# espIntrepid.net
KiCad netlist of a schematic drawn in EAGLE
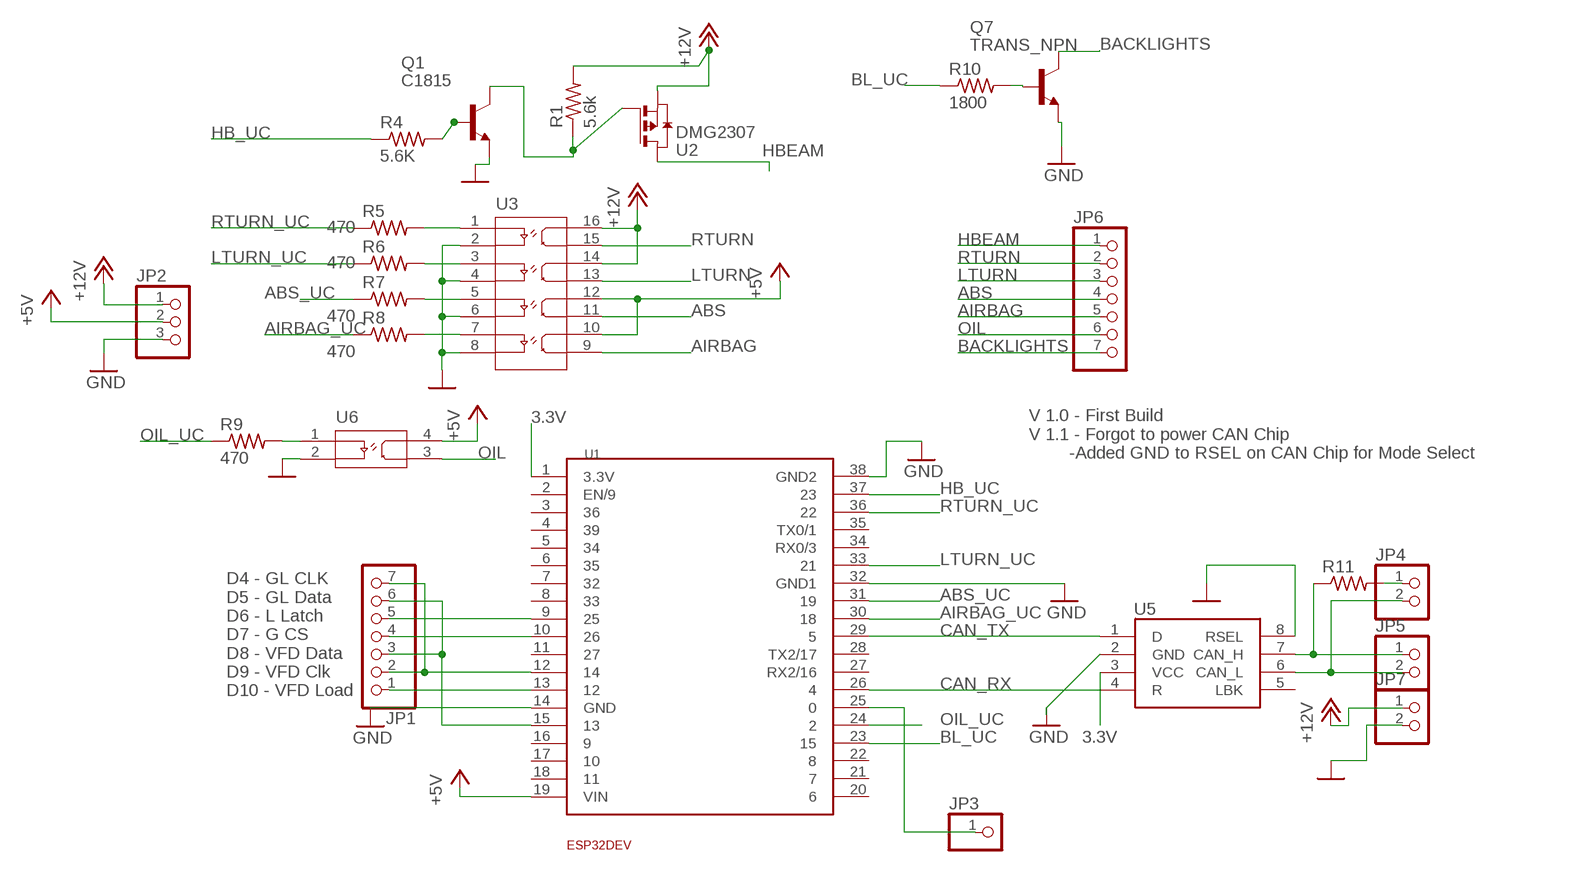
[diagram p0: schematic, sheet 1]

(export (version "E")
  (design (tool "Eeschema 10.0.6"))
  (components
    (comp (ref "JP1")
      (value "PINHD-1X7")
      (footprint "eagle-import:1X07")
      (libsource (lib "eagle-import") (part "PINHD-1X7"))
    )
    (comp (ref "JP2")
      (value "PINHD-1X3")
      (footprint "eagle-import:1X03")
      (libsource (lib "eagle-import") (part "PINHD-1X3"))
    )
    (comp (ref "JP3")
      (value "PINHD-1X1")
      (footprint "eagle-import:1X01")
      (libsource (lib "eagle-import") (part "PINHD-1X1"))
    )
    (comp (ref "JP4")
      (value "PINHD-1X2")
      (footprint "eagle-import:1X02")
      (libsource (lib "eagle-import") (part "PINHD-1X2"))
    )
    (comp (ref "JP5")
      (value "PINHD-1X2")
      (footprint "eagle-import:1X02")
      (libsource (lib "eagle-import") (part "PINHD-1X2"))
    )
    (comp (ref "JP6")
      (value "PINHD-1X7")
      (footprint "eagle-import:1X07")
      (libsource (lib "eagle-import") (part "pinhead_325_PINHD-1X7"))
    )
    (comp (ref "JP7")
      (value "PINHD-1X2")
      (footprint "eagle-import:1X02")
      (libsource (lib "eagle-import") (part "PINHD-1X2"))
    )
    (comp (ref "Q1")
      (value "C1815")
      (footprint "eagle-import:SOT-23")
      (libsource (lib "eagle-import") (part "TRANS_NPN"))
    )
    (comp (ref "Q7")
      (value "TRANS_NPN")
      (footprint "eagle-import:SOT-23")
      (libsource (lib "eagle-import") (part "TRANS_NPN"))
    )
    (comp (ref "R1")
      (value "5.6k")
      (footprint "eagle-import:M1206")
      (libsource (lib "eagle-import") (part "R-US_M1206"))
    )
    (comp (ref "R4")
      (value "5.6K")
      (footprint "eagle-import:M1206")
      (libsource (lib "eagle-import") (part "R-US_M1206"))
    )
    (comp (ref "R5")
      (value "470")
      (footprint "eagle-import:M1206")
      (libsource (lib "eagle-import") (part "R-US_M1206"))
    )
    (comp (ref "R6")
      (value "470")
      (footprint "eagle-import:M1206")
      (libsource (lib "eagle-import") (part "R-US_M1206"))
    )
    (comp (ref "R7")
      (value "470")
      (footprint "eagle-import:M1206")
      (libsource (lib "eagle-import") (part "R-US_M1206"))
    )
    (comp (ref "R8")
      (value "470")
      (footprint "eagle-import:M1206")
      (libsource (lib "eagle-import") (part "R-US_M1206"))
    )
    (comp (ref "R9")
      (value "470")
      (footprint "eagle-import:M1206")
      (libsource (lib "eagle-import") (part "R-US_M1206"))
    )
    (comp (ref "R10")
      (value "1800")
      (footprint "eagle-import:M1206")
      (libsource (lib "eagle-import") (part "R-US_M1206"))
    )
    (comp (ref "R11")
      (value "R-US_M1206")
      (footprint "eagle-import:M1206")
      (libsource (lib "eagle-import") (part "R-US_M1206"))
    )
    (comp (ref "U1")
      (value "ESP32DEV_38")
      (footprint "eagle-import:ESP32DEV_38")
      (libsource (lib "eagle-import") (part "ESP32DEV_38"))
    )
    (comp (ref "U2")
      (value "DMG2307")
      (footprint "eagle-import:SOT-23")
      (libsource (lib "eagle-import") (part "MOSFET_P"))
    )
    (comp (ref "U3")
      (value "LTV-847")
      (footprint "eagle-import:SM-16")
      (libsource (lib "eagle-import") (part "LTV-847"))
    )
    (comp (ref "U5")
      (value "SN65HVD233D")
      (footprint "eagle-import:SOIC-8")
      (libsource (lib "eagle-import") (part "SN65HVD233D"))
    )
    (comp (ref "U6")
      (value "LTV-817")
      (footprint "eagle-import:SM-4")
      (libsource (lib "eagle-import") (part "LTV-817"))
    )
  )
  (nets
    (net (code "1") (name "+5V") (class "Default")
      (node (ref "JP2") (pin "2") (pinfunction "2_2") (pintype "passive"))
      (node (ref "U1") (pin "19") (pinfunction "VIN_19") (pintype "bidirectional"))
      (node (ref "U3") (pin "10") (pinfunction "P$10_10") (pintype "bidirectional"))
      (node (ref "U3") (pin "12") (pinfunction "P$12_12") (pintype "bidirectional"))
      (node (ref "U6") (pin "4") (pinfunction "P$4_4") (pintype "bidirectional"))
    )
    (net (code "2") (name "+12V") (class "Default")
      (node (ref "JP2") (pin "1") (pinfunction "1_1") (pintype "passive"))
      (node (ref "JP7") (pin "1") (pinfunction "1_1") (pintype "passive"))
      (node (ref "R1") (pin "2") (pinfunction "2_2") (pintype "passive"))
      (node (ref "U2") (pin "2") (pinfunction "S_2") (pintype "passive"))
      (node (ref "U3") (pin "14") (pinfunction "P$14_14") (pintype "bidirectional"))
      (node (ref "U3") (pin "16") (pinfunction "P$16_16") (pintype "bidirectional"))
    )
    (net (code "3") (name "/3.3V") (class "Default")
      (node (ref "U1") (pin "1") (pinfunction "3.3V_1") (pintype "bidirectional"))
      (node (ref "U5") (pin "3") (pinfunction "VCC_3") (pintype "bidirectional"))
    )
    (net (code "4") (name "/ABS") (class "Default")
      (node (ref "JP6") (pin "4") (pinfunction "4_4") (pintype "passive"))
      (node (ref "U3") (pin "11") (pinfunction "P$11_11") (pintype "bidirectional"))
    )
    (net (code "5") (name "/ABS_UC") (class "Default")
      (node (ref "R7") (pin "1") (pinfunction "1_1") (pintype "passive"))
      (node (ref "U1") (pin "31") (pinfunction "19_31") (pintype "bidirectional"))
    )
    (net (code "6") (name "/AIRBAG") (class "Default")
      (node (ref "JP6") (pin "5") (pinfunction "5_5") (pintype "passive"))
      (node (ref "U3") (pin "9") (pinfunction "P$9_9") (pintype "bidirectional"))
    )
    (net (code "7") (name "/AIRBAG_UC") (class "Default")
      (node (ref "R8") (pin "1") (pinfunction "1_1") (pintype "passive"))
      (node (ref "U1") (pin "30") (pinfunction "18_30") (pintype "bidirectional"))
    )
    (net (code "8") (name "/BACKLIGHTS") (class "Default")
      (node (ref "JP6") (pin "7") (pinfunction "7_7") (pintype "passive"))
      (node (ref "Q7") (pin "3") (pinfunction "C_3") (pintype "passive"))
    )
    (net (code "9") (name "/BL_UC") (class "Default")
      (node (ref "R10") (pin "1") (pinfunction "1_1") (pintype "passive"))
      (node (ref "U1") (pin "23") (pinfunction "15_23") (pintype "bidirectional"))
    )
    (net (code "10") (name "/CAN_RX") (class "Default")
      (node (ref "U1") (pin "26") (pinfunction "4_26") (pintype "bidirectional"))
      (node (ref "U5") (pin "4") (pinfunction "R_4") (pintype "bidirectional"))
    )
    (net (code "11") (name "/CAN_TX") (class "Default")
      (node (ref "U1") (pin "29") (pinfunction "5_29") (pintype "bidirectional"))
      (node (ref "U5") (pin "1") (pinfunction "D_1") (pintype "bidirectional"))
    )
    (net (code "12") (name "/HBEAM") (class "Default")
      (node (ref "JP6") (pin "1") (pinfunction "1_1") (pintype "passive"))
      (node (ref "U2") (pin "3") (pinfunction "D_3") (pintype "passive"))
    )
    (net (code "13") (name "/HB_UC") (class "Default")
      (node (ref "R4") (pin "1") (pinfunction "1_1") (pintype "passive"))
      (node (ref "U1") (pin "37") (pinfunction "23_37") (pintype "bidirectional"))
    )
    (net (code "14") (name "/LTURN") (class "Default")
      (node (ref "JP6") (pin "3") (pinfunction "3_3") (pintype "passive"))
      (node (ref "U3") (pin "13") (pinfunction "P$13_13") (pintype "bidirectional"))
    )
    (net (code "15") (name "/LTURN_UC") (class "Default")
      (node (ref "R6") (pin "1") (pinfunction "1_1") (pintype "passive"))
      (node (ref "U1") (pin "33") (pinfunction "21_33") (pintype "bidirectional"))
    )
    (net (code "16") (name "/OIL") (class "Default")
      (node (ref "JP6") (pin "6") (pinfunction "6_6") (pintype "passive"))
      (node (ref "U6") (pin "3") (pinfunction "P$3_3") (pintype "bidirectional"))
    )
    (net (code "17") (name "/OIL_UC") (class "Default")
      (node (ref "R9") (pin "1") (pinfunction "1_1") (pintype "passive"))
      (node (ref "U1") (pin "24") (pinfunction "2_24") (pintype "bidirectional"))
    )
    (net (code "18") (name "/RTURN") (class "Default")
      (node (ref "JP6") (pin "2") (pinfunction "2_2") (pintype "passive"))
      (node (ref "U3") (pin "15") (pinfunction "P$15_15") (pintype "bidirectional"))
    )
    (net (code "19") (name "/RTURN_UC") (class "Default")
      (node (ref "R5") (pin "1") (pinfunction "1_1") (pintype "passive"))
      (node (ref "U1") (pin "36") (pinfunction "22_36") (pintype "bidirectional"))
    )
    (net (code "20") (name "GND") (class "Default")
      (node (ref "JP2") (pin "3") (pinfunction "3_3") (pintype "passive"))
      (node (ref "JP7") (pin "2") (pinfunction "2_2") (pintype "passive"))
      (node (ref "Q1") (pin "2") (pinfunction "E_2") (pintype "passive"))
      (node (ref "Q7") (pin "2") (pinfunction "E_2") (pintype "passive"))
      (node (ref "U1") (pin "14") (pinfunction "GND_14") (pintype "bidirectional"))
      (node (ref "U1") (pin "32") (pinfunction "GND1_32") (pintype "bidirectional"))
      (node (ref "U1") (pin "38") (pinfunction "GND2_38") (pintype "bidirectional"))
      (node (ref "U3") (pin "2") (pinfunction "P$2_2") (pintype "bidirectional"))
      (node (ref "U3") (pin "4") (pinfunction "P$4_4") (pintype "bidirectional"))
      (node (ref "U3") (pin "6") (pinfunction "P$6_6") (pintype "bidirectional"))
      (node (ref "U3") (pin "8") (pinfunction "P$8_8") (pintype "bidirectional"))
      (node (ref "U5") (pin "2") (pinfunction "GND_2") (pintype "bidirectional"))
      (node (ref "U5") (pin "8") (pinfunction "RSEL_8") (pintype "bidirectional"))
      (node (ref "U6") (pin "2") (pinfunction "P$2_2") (pintype "bidirectional"))
    )
    (net (code "21") (name "Net-(JP4-Pad1)") (class "Default")
      (node (ref "JP4") (pin "1") (pinfunction "1_1") (pintype "passive"))
      (node (ref "R11") (pin "2") (pinfunction "2_2") (pintype "passive"))
    )
    (net (code "22") (name "Net-(Q1-B)") (class "Default")
      (node (ref "Q1") (pin "1") (pinfunction "B_1") (pintype "passive"))
      (node (ref "R4") (pin "2") (pinfunction "2_2") (pintype "passive"))
    )
    (net (code "23") (name "Net-(Q1-C)") (class "Default")
      (node (ref "Q1") (pin "3") (pinfunction "C_3") (pintype "passive"))
      (node (ref "R1") (pin "1") (pinfunction "1_1") (pintype "passive"))
      (node (ref "U2") (pin "1") (pinfunction "G_1") (pintype "passive"))
    )
    (net (code "24") (name "Net-(Q7-B)") (class "Default")
      (node (ref "Q7") (pin "1") (pinfunction "B_1") (pintype "passive"))
      (node (ref "R10") (pin "2") (pinfunction "2_2") (pintype "passive"))
    )
    (net (code "25") (name "Net-(U1-0)") (class "Default")
      (node (ref "JP3") (pin "1") (pinfunction "1_1") (pintype "passive"))
      (node (ref "U1") (pin "25") (pinfunction "0_25") (pintype "bidirectional"))
    )
    (net (code "26") (name "Net-(U1-12)") (class "Default")
      (node (ref "JP1") (pin "1") (pinfunction "1_1") (pintype "passive"))
      (node (ref "U1") (pin "13") (pinfunction "12_13") (pintype "bidirectional"))
    )
    (net (code "27") (name "Net-(U1-13)") (class "Default")
      (node (ref "JP1") (pin "3") (pinfunction "3_3") (pintype "passive"))
      (node (ref "JP1") (pin "6") (pinfunction "6_6") (pintype "passive"))
      (node (ref "U1") (pin "15") (pinfunction "13_15") (pintype "bidirectional"))
    )
    (net (code "28") (name "Net-(U1-14)") (class "Default")
      (node (ref "JP1") (pin "2") (pinfunction "2_2") (pintype "passive"))
      (node (ref "JP1") (pin "7") (pinfunction "7_7") (pintype "passive"))
      (node (ref "U1") (pin "12") (pinfunction "14_12") (pintype "bidirectional"))
    )
    (net (code "29") (name "Net-(U1-25)") (class "Default")
      (node (ref "JP1") (pin "5") (pinfunction "5_5") (pintype "passive"))
      (node (ref "U1") (pin "9") (pinfunction "25_9") (pintype "bidirectional"))
    )
    (net (code "30") (name "Net-(U1-26)") (class "Default")
      (node (ref "JP1") (pin "4") (pinfunction "4_4") (pintype "passive"))
      (node (ref "U1") (pin "10") (pinfunction "26_10") (pintype "bidirectional"))
    )
    (net (code "31") (name "Net-(U3-P$1)") (class "Default")
      (node (ref "R5") (pin "2") (pinfunction "2_2") (pintype "passive"))
      (node (ref "U3") (pin "1") (pinfunction "P$1_1") (pintype "bidirectional"))
    )
    (net (code "32") (name "Net-(U3-P$3)") (class "Default")
      (node (ref "R6") (pin "2") (pinfunction "2_2") (pintype "passive"))
      (node (ref "U3") (pin "3") (pinfunction "P$3_3") (pintype "bidirectional"))
    )
    (net (code "33") (name "Net-(U3-P$5)") (class "Default")
      (node (ref "R7") (pin "2") (pinfunction "2_2") (pintype "passive"))
      (node (ref "U3") (pin "5") (pinfunction "P$5_5") (pintype "bidirectional"))
    )
    (net (code "34") (name "Net-(U3-P$7)") (class "Default")
      (node (ref "R8") (pin "2") (pinfunction "2_2") (pintype "passive"))
      (node (ref "U3") (pin "7") (pinfunction "P$7_7") (pintype "bidirectional"))
    )
    (net (code "35") (name "Net-(U5-CAN_H)") (class "Default")
      (node (ref "JP5") (pin "1") (pinfunction "1_1") (pintype "passive"))
      (node (ref "R11") (pin "1") (pinfunction "1_1") (pintype "passive"))
      (node (ref "U5") (pin "7") (pinfunction "CAN_H_7") (pintype "bidirectional"))
    )
    (net (code "36") (name "Net-(U5-CAN_L)") (class "Default")
      (node (ref "JP4") (pin "2") (pinfunction "2_2") (pintype "passive"))
      (node (ref "JP5") (pin "2") (pinfunction "2_2") (pintype "passive"))
      (node (ref "U5") (pin "6") (pinfunction "CAN_L_6") (pintype "bidirectional"))
    )
    (net (code "37") (name "Net-(U6-P$1)") (class "Default")
      (node (ref "R9") (pin "2") (pinfunction "2_2") (pintype "passive"))
      (node (ref "U6") (pin "1") (pinfunction "P$1_1") (pintype "bidirectional"))
    )
    (net (code "38") (name "unconnected-(U1-6-Pad20)") (class "Default")
      (node (ref "U1") (pin "20") (pinfunction "6_20") (pintype "bidirectional"))
    )
    (net (code "39") (name "unconnected-(U1-7-Pad21)") (class "Default")
      (node (ref "U1") (pin "21") (pinfunction "7_21") (pintype "bidirectional"))
    )
    (net (code "40") (name "unconnected-(U1-8-Pad22)") (class "Default")
      (node (ref "U1") (pin "22") (pinfunction "8_22") (pintype "bidirectional"))
    )
    (net (code "41") (name "unconnected-(U1-9-Pad16)") (class "Default")
      (node (ref "U1") (pin "16") (pinfunction "9_16") (pintype "bidirectional"))
    )
    (net (code "42") (name "unconnected-(U1-10-Pad17)") (class "Default")
      (node (ref "U1") (pin "17") (pinfunction "10_17") (pintype "bidirectional"))
    )
    (net (code "43") (name "unconnected-(U1-11-Pad18)") (class "Default")
      (node (ref "U1") (pin "18") (pinfunction "11_18") (pintype "bidirectional"))
    )
    (net (code "44") (name "unconnected-(U1-27-Pad11)") (class "Default")
      (node (ref "U1") (pin "11") (pinfunction "27_11") (pintype "bidirectional"))
    )
    (net (code "45") (name "unconnected-(U1-32-Pad7)") (class "Default")
      (node (ref "U1") (pin "7") (pinfunction "32_7") (pintype "bidirectional"))
    )
    (net (code "46") (name "unconnected-(U1-33-Pad8)") (class "Default")
      (node (ref "U1") (pin "8") (pinfunction "33_8") (pintype "bidirectional"))
    )
    (net (code "47") (name "unconnected-(U1-34-Pad5)") (class "Default")
      (node (ref "U1") (pin "5") (pinfunction "34_5") (pintype "bidirectional"))
    )
    (net (code "48") (name "unconnected-(U1-35-Pad6)") (class "Default")
      (node (ref "U1") (pin "6") (pinfunction "35_6") (pintype "bidirectional"))
    )
    (net (code "49") (name "unconnected-(U1-36-Pad3)") (class "Default")
      (node (ref "U1") (pin "3") (pinfunction "36_3") (pintype "bidirectional"))
    )
    (net (code "50") (name "unconnected-(U1-39-Pad4)") (class "Default")
      (node (ref "U1") (pin "4") (pinfunction "39_4") (pintype "bidirectional"))
    )
    (net (code "51") (name "unconnected-(U1-EN{slash}9-Pad2)") (class "Default")
      (node (ref "U1") (pin "2") (pinfunction "EN/9_2") (pintype "bidirectional"))
    )
    (net (code "52") (name "unconnected-(U1-RX0{slash}3-Pad34)") (class "Default")
      (node (ref "U1") (pin "34") (pinfunction "RX0/3_34") (pintype "bidirectional"))
    )
    (net (code "53") (name "unconnected-(U1-RX2{slash}16-Pad27)") (class "Default")
      (node (ref "U1") (pin "27") (pinfunction "RX2/16_27") (pintype "bidirectional"))
    )
    (net (code "54") (name "unconnected-(U1-TX0{slash}1-Pad35)") (class "Default")
      (node (ref "U1") (pin "35") (pinfunction "TX0/1_35") (pintype "bidirectional"))
    )
    (net (code "55") (name "unconnected-(U1-TX2{slash}17-Pad28)") (class "Default")
      (node (ref "U1") (pin "28") (pinfunction "TX2/17_28") (pintype "bidirectional"))
    )
    (net (code "56") (name "unconnected-(U5-LBK-Pad5)") (class "Default")
      (node (ref "U5") (pin "5") (pinfunction "LBK_5") (pintype "bidirectional"))
    )
  )
)
